# splitflap_01.net
KiCad netlist of a schematic drawn in EAGLE
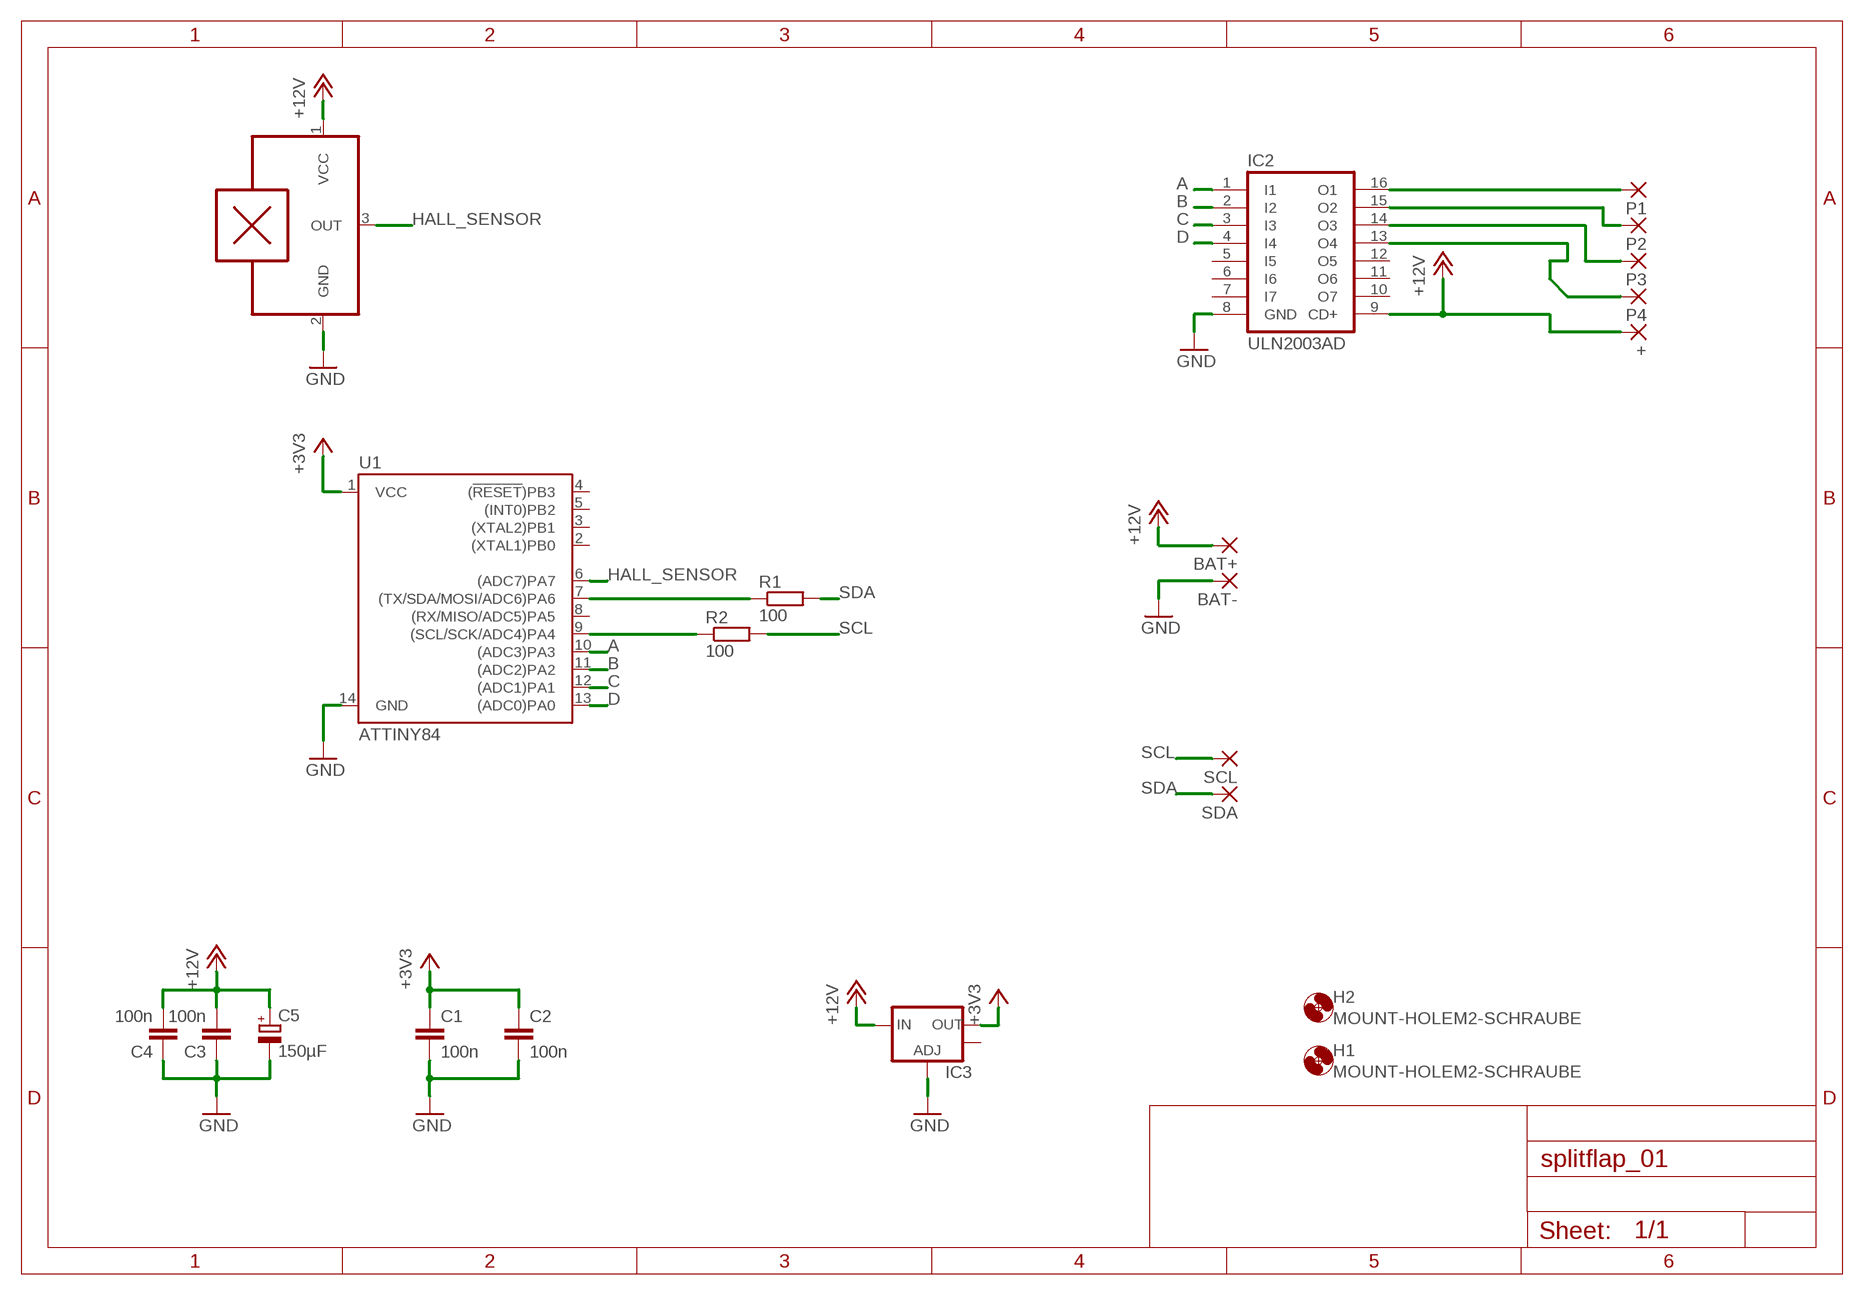
[diagram p0: schematic, sheet 1]

(export (version "E")
  (design (tool "Eeschema 10.0.6"))
  (components
    (comp (ref "+")
      (value "SMD5")
      (footprint "eagle-import:SMD2,54-5,08")
      (libsource (lib "eagle-import") (part "SMD5"))
    )
    (comp (ref "BAT+")
      (value "SMD5")
      (footprint "eagle-import:SMD2,54-5,08")
      (libsource (lib "eagle-import") (part "SMD5"))
    )
    (comp (ref "BAT-")
      (value "SMD5")
      (footprint "eagle-import:SMD2,54-5,08")
      (libsource (lib "eagle-import") (part "SMD5"))
    )
    (comp (ref "C1")
      (value "100n")
      (footprint "eagle-import:C0805")
      (libsource (lib "eagle-import") (part "C-EUC0805"))
    )
    (comp (ref "C2")
      (value "100n")
      (footprint "eagle-import:C0805")
      (libsource (lib "eagle-import") (part "C-EUC0805"))
    )
    (comp (ref "C3")
      (value "100n")
      (footprint "eagle-import:C0805")
      (libsource (lib "eagle-import") (part "C-EUC0805"))
    )
    (comp (ref "C4")
      (value "100n")
      (footprint "eagle-import:C0805")
      (libsource (lib "eagle-import") (part "C-EUC0805"))
    )
    (comp (ref "C5")
      (value "150µF")
      (footprint "eagle-import:SMC_D")
      (libsource (lib "eagle-import") (part "CPOL-EUSMCD"))
    )
    (comp (ref "H1")
      (value "MOUNT-HOLEM2-SCHRAUBE")
      (footprint "eagle-import:M2-SCHRAUBE")
      (libsource (lib "eagle-import") (part "MOUNT-HOLEM2-SCHRAUBE"))
    )
    (comp (ref "H2")
      (value "MOUNT-HOLEM2-SCHRAUBE")
      (footprint "eagle-import:M2-SCHRAUBE")
      (libsource (lib "eagle-import") (part "MOUNT-HOLEM2-SCHRAUBE"))
    )
    (comp (ref "IC2")
      (value "ULN2003AD")
      (footprint "eagle-import:SO16")
      (libsource (lib "eagle-import") (part "ULN2003AD"))
    )
    (comp (ref "IC3")
      (value "V_REG_LM1117SOT223")
      (footprint "eagle-import:SOT223")
      (libsource (lib "eagle-import") (part "V_REG_LM1117SOT223"))
    )
    (comp (ref "P1")
      (value "SMD5")
      (footprint "eagle-import:SMD2,54-5,08")
      (libsource (lib "eagle-import") (part "SMD5"))
    )
    (comp (ref "P2")
      (value "SMD5")
      (footprint "eagle-import:SMD2,54-5,08")
      (libsource (lib "eagle-import") (part "SMD5"))
    )
    (comp (ref "P3")
      (value "SMD5")
      (footprint "eagle-import:SMD2,54-5,08")
      (libsource (lib "eagle-import") (part "SMD5"))
    )
    (comp (ref "P4")
      (value "SMD5")
      (footprint "eagle-import:SMD2,54-5,08")
      (libsource (lib "eagle-import") (part "SMD5"))
    )
    (comp (ref "R1")
      (value "100")
      (footprint "eagle-import:R0805")
      (libsource (lib "eagle-import") (part "R-EU_R0805"))
    )
    (comp (ref "R2")
      (value "100")
      (footprint "eagle-import:R0805")
      (libsource (lib "eagle-import") (part "R-EU_R0805"))
    )
    (comp (ref "SCL")
      (value "SMD5")
      (footprint "eagle-import:SMD2,54-5,08")
      (libsource (lib "eagle-import") (part "SMD5"))
    )
    (comp (ref "SDA")
      (value "SMD5")
      (footprint "eagle-import:SMD2,54-5,08")
      (libsource (lib "eagle-import") (part "SMD5"))
    )
    (comp (ref "U$1")
      (value "A3144")
      (footprint "eagle-import:TO-92-LINE")
      (libsource (lib "eagle-import") (part "A3144"))
    )
    (comp (ref "U1")
      (value "ATTINY84")
      (footprint "eagle-import:SO14")
      (libsource (lib "eagle-import") (part "ATTINY84"))
    )
  )
  (nets
    (net (code "1") (name "+3V3") (class "Default")
      (node (ref "C1") (pin "1") (pinfunction "1_1") (pintype "passive"))
      (node (ref "C2") (pin "1") (pinfunction "1_1") (pintype "passive"))
      (node (ref "IC3") (pin "2") (pinfunction "OUT_2") (pintype "output"))
      (node (ref "U1") (pin "1") (pinfunction "VCC_1") (pintype "bidirectional"))
    )
    (net (code "2") (name "+12V") (class "Default")
      (node (ref "+") (pin "1") (pinfunction "P_1") (pintype "passive"))
      (node (ref "BAT+") (pin "1") (pinfunction "P_1") (pintype "passive"))
      (node (ref "C3") (pin "2") (pinfunction "2_2") (pintype "passive"))
      (node (ref "C4") (pin "2") (pinfunction "2_2") (pintype "passive"))
      (node (ref "C5") (pin "+") (pinfunction "+_+") (pintype "passive"))
      (node (ref "IC2") (pin "9") (pinfunction "CD+_9") (pintype "passive"))
      (node (ref "IC3") (pin "3") (pinfunction "IN_3") (pintype "input"))
      (node (ref "U$1") (pin "1") (pinfunction "VCC_1") (pintype "power_in"))
    )
    (net (code "3") (name "/A") (class "Default")
      (node (ref "IC2") (pin "1") (pinfunction "I1_1") (pintype "input"))
      (node (ref "U1") (pin "10") (pinfunction "(ADC3)PA3_10") (pintype "bidirectional"))
    )
    (net (code "4") (name "/B") (class "Default")
      (node (ref "IC2") (pin "2") (pinfunction "I2_2") (pintype "input"))
      (node (ref "U1") (pin "11") (pinfunction "(ADC2)PA2_11") (pintype "bidirectional"))
    )
    (net (code "5") (name "/C") (class "Default")
      (node (ref "IC2") (pin "3") (pinfunction "I3_3") (pintype "input"))
      (node (ref "U1") (pin "12") (pinfunction "(ADC1)PA1_12") (pintype "bidirectional"))
    )
    (net (code "6") (name "/D") (class "Default")
      (node (ref "IC2") (pin "4") (pinfunction "I4_4") (pintype "input"))
      (node (ref "U1") (pin "13") (pinfunction "(ADC0)PA0_13") (pintype "bidirectional"))
    )
    (net (code "7") (name "/HALL_SENSOR") (class "Default")
      (node (ref "U$1") (pin "3") (pinfunction "OUT_3") (pintype "bidirectional"))
      (node (ref "U1") (pin "6") (pinfunction "(ADC7)PA7_6") (pintype "bidirectional"))
    )
    (net (code "8") (name "/SCL") (class "Default")
      (node (ref "R2") (pin "2") (pinfunction "2_2") (pintype "passive"))
      (node (ref "SCL") (pin "1") (pinfunction "P_1") (pintype "passive"))
    )
    (net (code "9") (name "/SDA") (class "Default")
      (node (ref "R1") (pin "2") (pinfunction "2_2") (pintype "passive"))
      (node (ref "SDA") (pin "1") (pinfunction "P_1") (pintype "passive"))
    )
    (net (code "10") (name "GND") (class "Default")
      (node (ref "BAT-") (pin "1") (pinfunction "P_1") (pintype "passive"))
      (node (ref "C1") (pin "2") (pinfunction "2_2") (pintype "passive"))
      (node (ref "C2") (pin "2") (pinfunction "2_2") (pintype "passive"))
      (node (ref "C3") (pin "1") (pinfunction "1_1") (pintype "passive"))
      (node (ref "C4") (pin "1") (pinfunction "1_1") (pintype "passive"))
      (node (ref "C5") (pin "-") (pinfunction "-_-") (pintype "passive"))
      (node (ref "IC2") (pin "8") (pinfunction "GND_8") (pintype "power_in"))
      (node (ref "IC3") (pin "1") (pinfunction "ADJ_1") (pintype "input"))
      (node (ref "U$1") (pin "2") (pinfunction "GND_2") (pintype "bidirectional"))
      (node (ref "U1") (pin "14") (pinfunction "GND_14") (pintype "bidirectional"))
    )
    (net (code "11") (name "Net-(IC2-O1)") (class "Default")
      (node (ref "IC2") (pin "16") (pinfunction "O1_16") (pintype "open_collector"))
      (node (ref "P1") (pin "1") (pinfunction "P_1") (pintype "passive"))
    )
    (net (code "12") (name "Net-(IC2-O2)") (class "Default")
      (node (ref "IC2") (pin "15") (pinfunction "O2_15") (pintype "open_collector"))
      (node (ref "P2") (pin "1") (pinfunction "P_1") (pintype "passive"))
    )
    (net (code "13") (name "Net-(IC2-O3)") (class "Default")
      (node (ref "IC2") (pin "14") (pinfunction "O3_14") (pintype "open_collector"))
      (node (ref "P3") (pin "1") (pinfunction "P_1") (pintype "passive"))
    )
    (net (code "14") (name "Net-(IC2-O4)") (class "Default")
      (node (ref "IC2") (pin "13") (pinfunction "O4_13") (pintype "open_collector"))
      (node (ref "P4") (pin "1") (pinfunction "P_1") (pintype "passive"))
    )
    (net (code "15") (name "Net-(U1-(SCL{slash}SCK{slash}ADC4)PA4)") (class "Default")
      (node (ref "R2") (pin "1") (pinfunction "1_1") (pintype "passive"))
      (node (ref "U1") (pin "9") (pinfunction "(SCL/SCK/ADC4)PA4_9") (pintype "bidirectional"))
    )
    (net (code "16") (name "Net-(U1-(TX{slash}SDA{slash}MOSI{slash}ADC6)PA6)") (class "Default")
      (node (ref "R1") (pin "1") (pinfunction "1_1") (pintype "passive"))
      (node (ref "U1") (pin "7") (pinfunction "(TX/SDA/MOSI/ADC6)PA6_7") (pintype "bidirectional"))
    )
    (net (code "17") (name "unconnected-(IC2-I5-Pad5)") (class "Default")
      (node (ref "IC2") (pin "5") (pinfunction "I5_5") (pintype "input"))
    )
    (net (code "18") (name "unconnected-(IC2-I6-Pad6)") (class "Default")
      (node (ref "IC2") (pin "6") (pinfunction "I6_6") (pintype "input"))
    )
    (net (code "19") (name "unconnected-(IC2-I7-Pad7)") (class "Default")
      (node (ref "IC2") (pin "7") (pinfunction "I7_7") (pintype "input"))
    )
    (net (code "20") (name "unconnected-(IC2-O5-Pad12)") (class "Default")
      (node (ref "IC2") (pin "12") (pinfunction "O5_12") (pintype "open_collector"))
    )
    (net (code "21") (name "unconnected-(IC2-O6-Pad11)") (class "Default")
      (node (ref "IC2") (pin "11") (pinfunction "O6_11") (pintype "open_collector"))
    )
    (net (code "22") (name "unconnected-(IC2-O7-Pad10)") (class "Default")
      (node (ref "IC2") (pin "10") (pinfunction "O7_10") (pintype "open_collector"))
    )
    (net (code "23") (name "unconnected-(IC3-OUT-Pad4)") (class "Default")
      (node (ref "IC3") (pin "4") (pinfunction "OUT_4") (pintype "output"))
    )
    (net (code "24") (name "unconnected-(U1-(INT0)PB2-Pad5)") (class "Default")
      (node (ref "U1") (pin "5") (pinfunction "(INT0)PB2_5") (pintype "bidirectional"))
    )
    (net (code "25") (name "unconnected-(U1-(RX{slash}MISO{slash}ADC5)PA5-Pad8)") (class "Default")
      (node (ref "U1") (pin "8") (pinfunction "(RX/MISO/ADC5)PA5_8") (pintype "bidirectional"))
    )
    (net (code "26") (name "unconnected-(U1-(XTAL1)PB0-Pad2)") (class "Default")
      (node (ref "U1") (pin "2") (pinfunction "(XTAL1)PB0_2") (pintype "bidirectional"))
    )
    (net (code "27") (name "unconnected-(U1-(XTAL2)PB1-Pad3)") (class "Default")
      (node (ref "U1") (pin "3") (pinfunction "(XTAL2)PB1_3") (pintype "bidirectional"))
    )
    (net (code "28") (name "unconnected-(U1-(~{RESET})PB3-Pad4)") (class "Default")
      (node (ref "U1") (pin "4") (pinfunction "(~{RESET})PB3_4") (pintype "bidirectional"))
    )
  )
)
